# 6WP.net
KiCad netlist of a schematic drawn in EAGLE
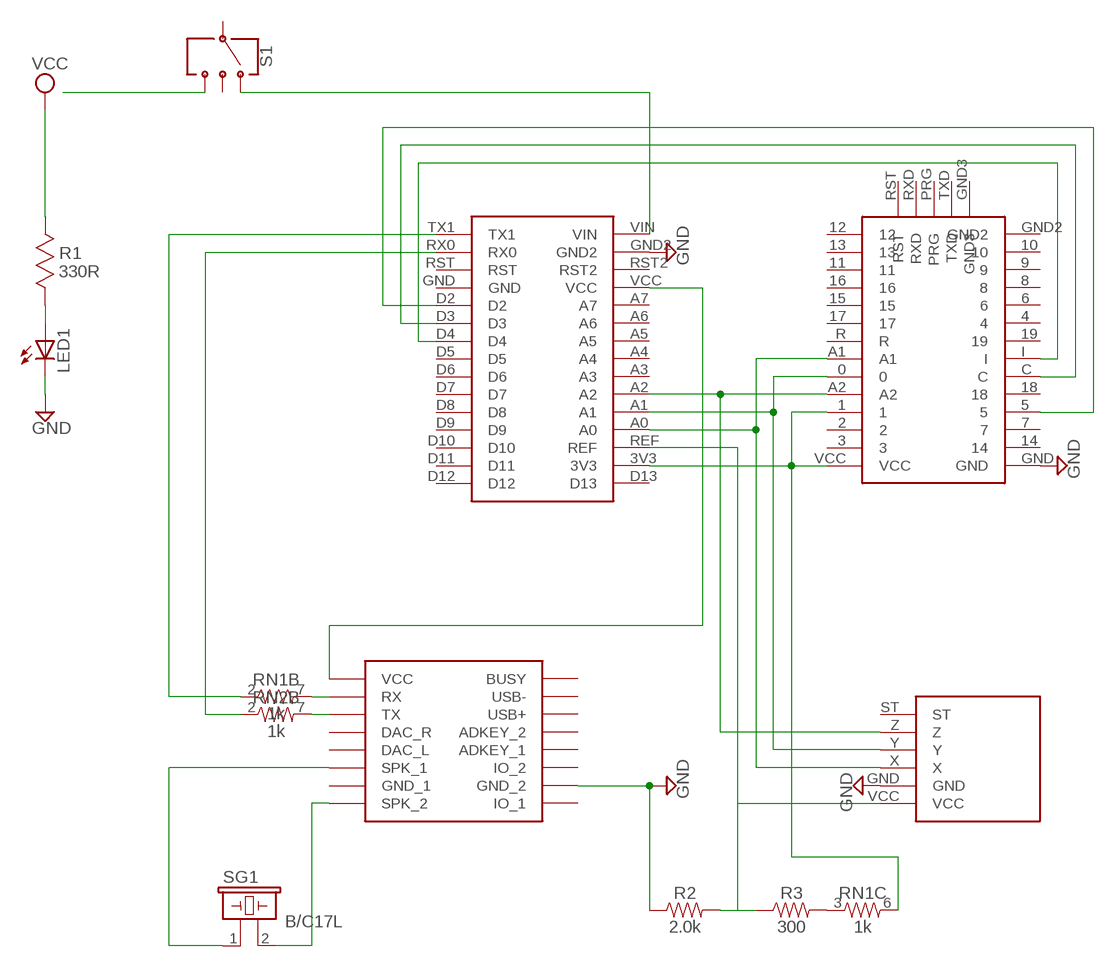
[diagram p0: schematic, sheet 1]
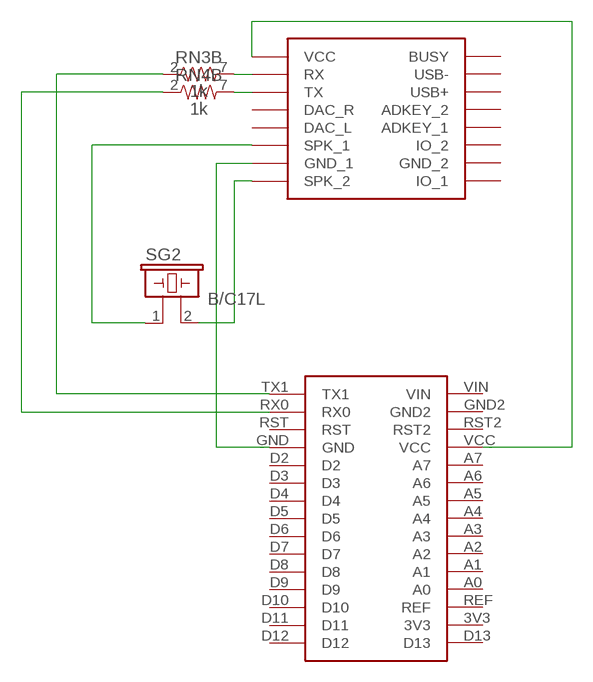
[diagram p1: schematic, sheet 2]

(export (version "E")
  (design (tool "Eeschema 10.0.6"))
  (components
    (comp (ref "A3")
      (value "ARDUINONANO")
      (footprint "eagle-import:ARDUINONANO")
      (libsource (lib "eagle-import") (part "ARDUINONANO"))
    )
    (comp (ref "RN3")
      (value "1k")
      (footprint "eagle-import:0805-ARV")
      (libsource (lib "eagle-import") (part "1KOHM-ARRAY(4)-0805_ARV-1/10W-5%"))
    )
    (comp (ref "RN4")
      (value "1k")
      (footprint "eagle-import:0805-ARV")
      (libsource (lib "eagle-import") (part "1KOHM-ARRAY(4)-0805_ARV-1/10W-5%"))
    )
    (comp (ref "SG2")
      (value "B/C17L")
      (footprint "eagle-import:B_C17L")
      (libsource (lib "eagle-import") (part "B/C17L"))
    )
    (comp (ref "U$1")
      (value "DFPLAYER")
      (footprint "eagle-import:DFPLAYER")
      (libsource (lib "eagle-import") (part "DFPLAYER"))
    )
    (comp (ref "A1")
      (value "ARDUINONANO")
      (footprint "eagle-import:ARDUINONANO")
      (libsource (lib "eagle-import") (part "ARDUINONANO"))
    )
    (comp (ref "A2")
      (value "ADXL335")
      (footprint "eagle-import:ADXL335")
      (libsource (lib "eagle-import") (part "ADXL335"))
    )
    (comp (ref "A4")
      (value "TWELITEDIP")
      (footprint "eagle-import:TWELITEDIP")
      (libsource (lib "eagle-import") (part "TWELITEDIP"))
    )
    (comp (ref "LED1")
      (value "LEDCHIP-LED0603")
      (footprint "eagle-import:CHIP-LED0603")
      (libsource (lib "eagle-import") (part "LEDCHIP-LED0603"))
    )
    (comp (ref "R1")
      (value "330R")
      (footprint "eagle-import:RESC1608X60N")
      (fields (field (name "MPN") "MC0.063W06031%330R") (field (name "TOLERANCE") "±1%"))
      (libsource (lib "eagle-import") (part "MC0.063W06031%330R"))
    )
    (comp (ref "R2")
      (value "2.0k")
      (footprint "eagle-import:0603")
      (libsource (lib "eagle-import") (part "2.0KOHM-0603-1/10W-5%"))
    )
    (comp (ref "R3")
      (value "300")
      (footprint "eagle-import:0603")
      (libsource (lib "eagle-import") (part "300OHM-0603-1/10W-1%"))
    )
    (comp (ref "RN1")
      (value "1k")
      (footprint "eagle-import:0805-ARV")
      (libsource (lib "eagle-import") (part "1KOHM-ARRAY(4)-0805_ARV-1/10W-5%"))
    )
    (comp (ref "RN2")
      (value "1k")
      (footprint "eagle-import:0805-ARV")
      (libsource (lib "eagle-import") (part "1KOHM-ARRAY(4)-0805_ARV-1/10W-5%"))
    )
    (comp (ref "S1")
      (value "SWITCH-SP3T-SMD")
      (footprint "eagle-import:SWITCH_SP3T_SMD")
      (libsource (lib "eagle-import") (part "SWITCH-SP3T-SMD"))
    )
    (comp (ref "SG1")
      (value "B/C17L")
      (footprint "eagle-import:B_C17L")
      (libsource (lib "eagle-import") (part "B/C17L"))
    )
    (comp (ref "U$2")
      (value "DFPLAYER")
      (footprint "eagle-import:DFPLAYER")
      (libsource (lib "eagle-import") (part "DFPLAYER"))
    )
  )
  (nets
    (net (code "1") (name "GND") (class "Default")
      (node (ref "A1") (pin "GND2") (pinfunction "GND2_GND2") (pintype "bidirectional"))
      (node (ref "A2") (pin "GND") (pinfunction "GND_GND") (pintype "bidirectional"))
      (node (ref "A4") (pin "GND") (pinfunction "GND_GND") (pintype "bidirectional"))
      (node (ref "LED1") (pin "C") (pinfunction "C_C") (pintype "passive"))
      (node (ref "R2") (pin "1") (pinfunction "1_1") (pintype "passive"))
      (node (ref "U$2") (pin "GND_2") (pinfunction "GND_2_GND_2") (pintype "bidirectional"))
    )
    (net (code "2") (name "Net-(A1-PadA0)") (class "Default")
      (node (ref "A1") (pin "A0") (pinfunction "A0_A0") (pintype "bidirectional"))
      (node (ref "A2") (pin "X") (pinfunction "X_X") (pintype "bidirectional"))
      (node (ref "A4") (pin "A1") (pinfunction "A1_A1") (pintype "bidirectional"))
    )
    (net (code "3") (name "Net-(A1-PadA1)") (class "Default")
      (node (ref "A1") (pin "A1") (pinfunction "A1_A1") (pintype "bidirectional"))
      (node (ref "A2") (pin "Y") (pinfunction "Y_Y") (pintype "bidirectional"))
      (node (ref "A4") (pin "0") (pinfunction "0_0") (pintype "bidirectional"))
    )
    (net (code "4") (name "Net-(A1-PadA2)") (class "Default")
      (node (ref "A1") (pin "A2") (pinfunction "A2_A2") (pintype "bidirectional"))
      (node (ref "A2") (pin "Z") (pinfunction "Z_Z") (pintype "bidirectional"))
      (node (ref "A4") (pin "A2") (pinfunction "A2_A2") (pintype "bidirectional"))
    )
    (net (code "5") (name "Net-(A1-PadD2)") (class "Default")
      (node (ref "A1") (pin "D2") (pinfunction "D2_D2") (pintype "bidirectional"))
      (node (ref "A4") (pin "5") (pinfunction "5_5") (pintype "bidirectional"))
    )
    (net (code "6") (name "Net-(A1-PadD3)") (class "Default")
      (node (ref "A1") (pin "D3") (pinfunction "D3_D3") (pintype "bidirectional"))
      (node (ref "A4") (pin "C") (pinfunction "C_C") (pintype "bidirectional"))
    )
    (net (code "7") (name "Net-(A1-PadD4)") (class "Default")
      (node (ref "A1") (pin "D4") (pinfunction "D4_D4") (pintype "bidirectional"))
      (node (ref "A4") (pin "I") (pinfunction "I_I") (pintype "bidirectional"))
    )
    (net (code "8") (name "Net-(A1-PadREF)") (class "Default")
      (node (ref "A1") (pin "REF") (pinfunction "REF_REF") (pintype "bidirectional"))
      (node (ref "A2") (pin "VCC") (pinfunction "VCC_VCC") (pintype "bidirectional"))
      (node (ref "R2") (pin "2") (pinfunction "2_2") (pintype "passive"))
      (node (ref "R3") (pin "1") (pinfunction "1_1") (pintype "passive"))
    )
    (net (code "9") (name "Net-(A1-PadVCC)") (class "Default")
      (node (ref "A1") (pin "VCC") (pinfunction "VCC_VCC") (pintype "bidirectional"))
      (node (ref "U$2") (pin "VCC") (pinfunction "VCC_VCC") (pintype "bidirectional"))
    )
    (net (code "10") (name "Net-(A1-PadVIN)") (class "Default")
      (node (ref "A1") (pin "VIN") (pinfunction "VIN_VIN") (pintype "bidirectional"))
      (node (ref "S1") (pin "1") (pinfunction "1_1") (pintype "bidirectional"))
    )
    (net (code "11") (name "Net-(A3-PadGND)") (class "Default")
      (node (ref "A3") (pin "GND") (pinfunction "GND_GND") (pintype "bidirectional"))
      (node (ref "U$1") (pin "GND_1") (pinfunction "GND_1_GND_1") (pintype "bidirectional"))
    )
    (net (code "12") (name "Net-(A3-PadVCC)") (class "Default")
      (node (ref "A3") (pin "VCC") (pinfunction "VCC_VCC") (pintype "bidirectional"))
      (node (ref "U$1") (pin "VCC") (pinfunction "VCC_VCC") (pintype "bidirectional"))
    )
    (net (code "13") (name "Net-(R1-R2)") (class "Default")
      (node (ref "LED1") (pin "A") (pinfunction "A_A") (pintype "passive"))
      (node (ref "R1") (pin "2") (pinfunction "R2_2") (pintype "passive"))
    )
    (net (code "14") (name "Net-(RN1B-1)") (class "Default")
      (node (ref "A1") (pin "TX1") (pinfunction "TX1_TX1") (pintype "bidirectional"))
      (node (ref "RN1") (pin "2") (pinfunction "1_2") (pintype "passive"))
    )
    (net (code "15") (name "Net-(RN1B-2)") (class "Default")
      (node (ref "RN1") (pin "7") (pinfunction "2_7") (pintype "passive"))
      (node (ref "U$2") (pin "RX") (pinfunction "RX_RX") (pintype "bidirectional"))
    )
    (net (code "16") (name "Net-(RN1C-1)") (class "Default")
      (node (ref "R3") (pin "2") (pinfunction "2_2") (pintype "passive"))
      (node (ref "RN1") (pin "3") (pinfunction "1_3") (pintype "passive"))
    )
    (net (code "17") (name "Net-(RN1C-2)") (class "Default")
      (node (ref "A1") (pin "3V3") (pinfunction "3V3_3V3") (pintype "bidirectional"))
      (node (ref "A4") (pin "1") (pinfunction "1_1") (pintype "bidirectional"))
      (node (ref "A4") (pin "VCC") (pinfunction "VCC_VCC") (pintype "bidirectional"))
      (node (ref "RN1") (pin "6") (pinfunction "2_6") (pintype "passive"))
    )
    (net (code "18") (name "Net-(RN2B-1)") (class "Default")
      (node (ref "A1") (pin "RX0") (pinfunction "RX0_RX0") (pintype "bidirectional"))
      (node (ref "RN2") (pin "2") (pinfunction "1_2") (pintype "passive"))
    )
    (net (code "19") (name "Net-(RN2B-2)") (class "Default")
      (node (ref "RN2") (pin "7") (pinfunction "2_7") (pintype "passive"))
      (node (ref "U$2") (pin "TX") (pinfunction "TX_TX") (pintype "bidirectional"))
    )
    (net (code "20") (name "Net-(RN3B-1)") (class "Default")
      (node (ref "A3") (pin "TX1") (pinfunction "TX1_TX1") (pintype "bidirectional"))
      (node (ref "RN3") (pin "2") (pinfunction "1_2") (pintype "passive"))
    )
    (net (code "21") (name "Net-(RN3B-2)") (class "Default")
      (node (ref "RN3") (pin "7") (pinfunction "2_7") (pintype "passive"))
      (node (ref "U$1") (pin "RX") (pinfunction "RX_RX") (pintype "bidirectional"))
    )
    (net (code "22") (name "Net-(RN4B-1)") (class "Default")
      (node (ref "A3") (pin "RX0") (pinfunction "RX0_RX0") (pintype "bidirectional"))
      (node (ref "RN4") (pin "2") (pinfunction "1_2") (pintype "passive"))
    )
    (net (code "23") (name "Net-(RN4B-2)") (class "Default")
      (node (ref "RN4") (pin "7") (pinfunction "2_7") (pintype "passive"))
      (node (ref "U$1") (pin "TX") (pinfunction "TX_TX") (pintype "bidirectional"))
    )
    (net (code "24") (name "Net-(U$1-SPK_1)") (class "Default")
      (node (ref "SG2") (pin "1") (pinfunction "1_1") (pintype "passive"))
      (node (ref "U$1") (pin "SPK1") (pinfunction "SPK_1_SPK1") (pintype "bidirectional"))
    )
    (net (code "25") (name "Net-(U$1-SPK_2)") (class "Default")
      (node (ref "SG2") (pin "2") (pinfunction "2_2") (pintype "passive"))
      (node (ref "U$1") (pin "SPK2") (pinfunction "SPK_2_SPK2") (pintype "bidirectional"))
    )
    (net (code "26") (name "Net-(U$2-SPK_1)") (class "Default")
      (node (ref "SG1") (pin "1") (pinfunction "1_1") (pintype "passive"))
      (node (ref "U$2") (pin "SPK1") (pinfunction "SPK_1_SPK1") (pintype "bidirectional"))
    )
    (net (code "27") (name "Net-(U$2-SPK_2)") (class "Default")
      (node (ref "SG1") (pin "2") (pinfunction "2_2") (pintype "passive"))
      (node (ref "U$2") (pin "SPK2") (pinfunction "SPK_2_SPK2") (pintype "bidirectional"))
    )
    (net (code "28") (name "VCC") (class "Default")
      (node (ref "R1") (pin "1") (pinfunction "R1_1") (pintype "passive"))
    )
    (net (code "29") (name "unconnected-(A1-PadA3)") (class "Default")
      (node (ref "A1") (pin "A3") (pinfunction "A3_A3") (pintype "bidirectional"))
    )
    (net (code "30") (name "unconnected-(A1-PadA4)") (class "Default")
      (node (ref "A1") (pin "A4") (pinfunction "A4_A4") (pintype "bidirectional"))
    )
    (net (code "31") (name "unconnected-(A1-PadA5)") (class "Default")
      (node (ref "A1") (pin "A5") (pinfunction "A5_A5") (pintype "bidirectional"))
    )
    (net (code "32") (name "unconnected-(A1-PadA6)") (class "Default")
      (node (ref "A1") (pin "A6") (pinfunction "A6_A6") (pintype "bidirectional"))
    )
    (net (code "33") (name "unconnected-(A1-PadA7)") (class "Default")
      (node (ref "A1") (pin "A7") (pinfunction "A7_A7") (pintype "bidirectional"))
    )
    (net (code "34") (name "unconnected-(A1-PadD5)") (class "Default")
      (node (ref "A1") (pin "D5") (pinfunction "D5_D5") (pintype "bidirectional"))
    )
    (net (code "35") (name "unconnected-(A1-PadD6)") (class "Default")
      (node (ref "A1") (pin "D6") (pinfunction "D6_D6") (pintype "bidirectional"))
    )
    (net (code "36") (name "unconnected-(A1-PadD7)") (class "Default")
      (node (ref "A1") (pin "D7") (pinfunction "D7_D7") (pintype "bidirectional"))
    )
    (net (code "37") (name "unconnected-(A1-PadD8)") (class "Default")
      (node (ref "A1") (pin "D8") (pinfunction "D8_D8") (pintype "bidirectional"))
    )
    (net (code "38") (name "unconnected-(A1-PadD9)") (class "Default")
      (node (ref "A1") (pin "D9") (pinfunction "D9_D9") (pintype "bidirectional"))
    )
    (net (code "39") (name "unconnected-(A1-PadD10)") (class "Default")
      (node (ref "A1") (pin "D10") (pinfunction "D10_D10") (pintype "bidirectional"))
    )
    (net (code "40") (name "unconnected-(A1-PadD11)") (class "Default")
      (node (ref "A1") (pin "D11") (pinfunction "D11_D11") (pintype "bidirectional"))
    )
    (net (code "41") (name "unconnected-(A1-PadD12)") (class "Default")
      (node (ref "A1") (pin "D12") (pinfunction "D12_D12") (pintype "bidirectional"))
    )
    (net (code "42") (name "unconnected-(A1-PadD13)") (class "Default")
      (node (ref "A1") (pin "D13") (pinfunction "D13_D13") (pintype "bidirectional"))
    )
    (net (code "43") (name "unconnected-(A1-PadGND)") (class "Default")
      (node (ref "A1") (pin "GND") (pinfunction "GND_GND") (pintype "bidirectional"))
    )
    (net (code "44") (name "unconnected-(A1-PadRST)") (class "Default")
      (node (ref "A1") (pin "RST") (pinfunction "RST_RST") (pintype "bidirectional"))
    )
    (net (code "45") (name "unconnected-(A1-PadRST2)") (class "Default")
      (node (ref "A1") (pin "RST2") (pinfunction "RST2_RST2") (pintype "bidirectional"))
    )
    (net (code "46") (name "unconnected-(A2-PadST)") (class "Default")
      (node (ref "A2") (pin "ST") (pinfunction "ST_ST") (pintype "bidirectional"))
    )
    (net (code "47") (name "unconnected-(A3-Pad3V3)") (class "Default")
      (node (ref "A3") (pin "3V3") (pinfunction "3V3_3V3") (pintype "bidirectional"))
    )
    (net (code "48") (name "unconnected-(A3-PadA0)") (class "Default")
      (node (ref "A3") (pin "A0") (pinfunction "A0_A0") (pintype "bidirectional"))
    )
    (net (code "49") (name "unconnected-(A3-PadA1)") (class "Default")
      (node (ref "A3") (pin "A1") (pinfunction "A1_A1") (pintype "bidirectional"))
    )
    (net (code "50") (name "unconnected-(A3-PadA2)") (class "Default")
      (node (ref "A3") (pin "A2") (pinfunction "A2_A2") (pintype "bidirectional"))
    )
    (net (code "51") (name "unconnected-(A3-PadA3)") (class "Default")
      (node (ref "A3") (pin "A3") (pinfunction "A3_A3") (pintype "bidirectional"))
    )
    (net (code "52") (name "unconnected-(A3-PadA4)") (class "Default")
      (node (ref "A3") (pin "A4") (pinfunction "A4_A4") (pintype "bidirectional"))
    )
    (net (code "53") (name "unconnected-(A3-PadA5)") (class "Default")
      (node (ref "A3") (pin "A5") (pinfunction "A5_A5") (pintype "bidirectional"))
    )
    (net (code "54") (name "unconnected-(A3-PadA6)") (class "Default")
      (node (ref "A3") (pin "A6") (pinfunction "A6_A6") (pintype "bidirectional"))
    )
    (net (code "55") (name "unconnected-(A3-PadA7)") (class "Default")
      (node (ref "A3") (pin "A7") (pinfunction "A7_A7") (pintype "bidirectional"))
    )
    (net (code "56") (name "unconnected-(A3-PadD2)") (class "Default")
      (node (ref "A3") (pin "D2") (pinfunction "D2_D2") (pintype "bidirectional"))
    )
    (net (code "57") (name "unconnected-(A3-PadD3)") (class "Default")
      (node (ref "A3") (pin "D3") (pinfunction "D3_D3") (pintype "bidirectional"))
    )
    (net (code "58") (name "unconnected-(A3-PadD4)") (class "Default")
      (node (ref "A3") (pin "D4") (pinfunction "D4_D4") (pintype "bidirectional"))
    )
    (net (code "59") (name "unconnected-(A3-PadD5)") (class "Default")
      (node (ref "A3") (pin "D5") (pinfunction "D5_D5") (pintype "bidirectional"))
    )
    (net (code "60") (name "unconnected-(A3-PadD6)") (class "Default")
      (node (ref "A3") (pin "D6") (pinfunction "D6_D6") (pintype "bidirectional"))
    )
    (net (code "61") (name "unconnected-(A3-PadD7)") (class "Default")
      (node (ref "A3") (pin "D7") (pinfunction "D7_D7") (pintype "bidirectional"))
    )
    (net (code "62") (name "unconnected-(A3-PadD8)") (class "Default")
      (node (ref "A3") (pin "D8") (pinfunction "D8_D8") (pintype "bidirectional"))
    )
    (net (code "63") (name "unconnected-(A3-PadD9)") (class "Default")
      (node (ref "A3") (pin "D9") (pinfunction "D9_D9") (pintype "bidirectional"))
    )
    (net (code "64") (name "unconnected-(A3-PadD10)") (class "Default")
      (node (ref "A3") (pin "D10") (pinfunction "D10_D10") (pintype "bidirectional"))
    )
    (net (code "65") (name "unconnected-(A3-PadD11)") (class "Default")
      (node (ref "A3") (pin "D11") (pinfunction "D11_D11") (pintype "bidirectional"))
    )
    (net (code "66") (name "unconnected-(A3-PadD12)") (class "Default")
      (node (ref "A3") (pin "D12") (pinfunction "D12_D12") (pintype "bidirectional"))
    )
    (net (code "67") (name "unconnected-(A3-PadD13)") (class "Default")
      (node (ref "A3") (pin "D13") (pinfunction "D13_D13") (pintype "bidirectional"))
    )
    (net (code "68") (name "unconnected-(A3-PadGND2)") (class "Default")
      (node (ref "A3") (pin "GND2") (pinfunction "GND2_GND2") (pintype "bidirectional"))
    )
    (net (code "69") (name "unconnected-(A3-PadREF)") (class "Default")
      (node (ref "A3") (pin "REF") (pinfunction "REF_REF") (pintype "bidirectional"))
    )
    (net (code "70") (name "unconnected-(A3-PadRST)") (class "Default")
      (node (ref "A3") (pin "RST") (pinfunction "RST_RST") (pintype "bidirectional"))
    )
    (net (code "71") (name "unconnected-(A3-PadRST2)") (class "Default")
      (node (ref "A3") (pin "RST2") (pinfunction "RST2_RST2") (pintype "bidirectional"))
    )
    (net (code "72") (name "unconnected-(A3-PadVIN)") (class "Default")
      (node (ref "A3") (pin "VIN") (pinfunction "VIN_VIN") (pintype "bidirectional"))
    )
    (net (code "73") (name "unconnected-(A4-Pad2)") (class "Default")
      (node (ref "A4") (pin "2") (pinfunction "2_2") (pintype "bidirectional"))
    )
    (net (code "74") (name "unconnected-(A4-Pad3)") (class "Default")
      (node (ref "A4") (pin "3") (pinfunction "3_3") (pintype "bidirectional"))
    )
    (net (code "75") (name "unconnected-(A4-Pad4)") (class "Default")
      (node (ref "A4") (pin "4") (pinfunction "4_4") (pintype "bidirectional"))
    )
    (net (code "76") (name "unconnected-(A4-Pad6)") (class "Default")
      (node (ref "A4") (pin "6") (pinfunction "6_6") (pintype "bidirectional"))
    )
    (net (code "77") (name "unconnected-(A4-Pad7)") (class "Default")
      (node (ref "A4") (pin "7") (pinfunction "7_7") (pintype "bidirectional"))
    )
    (net (code "78") (name "unconnected-(A4-Pad8)") (class "Default")
      (node (ref "A4") (pin "8") (pinfunction "8_8") (pintype "bidirectional"))
    )
    (net (code "79") (name "unconnected-(A4-Pad9)") (class "Default")
      (node (ref "A4") (pin "9") (pinfunction "9_9") (pintype "bidirectional"))
    )
    (net (code "80") (name "unconnected-(A4-Pad10)") (class "Default")
      (node (ref "A4") (pin "10") (pinfunction "10_10") (pintype "bidirectional"))
    )
    (net (code "81") (name "unconnected-(A4-Pad11)") (class "Default")
      (node (ref "A4") (pin "11") (pinfunction "11_11") (pintype "bidirectional"))
    )
    (net (code "82") (name "unconnected-(A4-Pad12)") (class "Default")
      (node (ref "A4") (pin "12") (pinfunction "12_12") (pintype "bidirectional"))
    )
    (net (code "83") (name "unconnected-(A4-Pad13)") (class "Default")
      (node (ref "A4") (pin "13") (pinfunction "13_13") (pintype "bidirectional"))
    )
    (net (code "84") (name "unconnected-(A4-Pad14)") (class "Default")
      (node (ref "A4") (pin "14") (pinfunction "14_14") (pintype "bidirectional"))
    )
    (net (code "85") (name "unconnected-(A4-Pad15)") (class "Default")
      (node (ref "A4") (pin "15") (pinfunction "15_15") (pintype "bidirectional"))
    )
    (net (code "86") (name "unconnected-(A4-Pad16)") (class "Default")
      (node (ref "A4") (pin "16") (pinfunction "16_16") (pintype "bidirectional"))
    )
    (net (code "87") (name "unconnected-(A4-Pad17)") (class "Default")
      (node (ref "A4") (pin "17") (pinfunction "17_17") (pintype "bidirectional"))
    )
    (net (code "88") (name "unconnected-(A4-Pad18)") (class "Default")
      (node (ref "A4") (pin "18") (pinfunction "18_18") (pintype "bidirectional"))
    )
    (net (code "89") (name "unconnected-(A4-Pad19)") (class "Default")
      (node (ref "A4") (pin "19") (pinfunction "19_19") (pintype "bidirectional"))
    )
    (net (code "90") (name "unconnected-(A4-PadGND2)") (class "Default")
      (node (ref "A4") (pin "GND2") (pinfunction "GND2_GND2") (pintype "bidirectional"))
    )
    (net (code "91") (name "unconnected-(A4-PadGND3)") (class "Default")
      (node (ref "A4") (pin "GND3") (pinfunction "GND3_GND3") (pintype "bidirectional"))
    )
    (net (code "92") (name "unconnected-(A4-PadPRG)") (class "Default")
      (node (ref "A4") (pin "PRG") (pinfunction "PRG_PRG") (pintype "bidirectional"))
    )
    (net (code "93") (name "unconnected-(A4-PadR)") (class "Default")
      (node (ref "A4") (pin "R") (pinfunction "R_R") (pintype "bidirectional"))
    )
    (net (code "94") (name "unconnected-(A4-PadRST)") (class "Default")
      (node (ref "A4") (pin "RST") (pinfunction "RST_RST") (pintype "bidirectional"))
    )
    (net (code "95") (name "unconnected-(A4-PadRXD)") (class "Default")
      (node (ref "A4") (pin "RXD") (pinfunction "RXD_RXD") (pintype "bidirectional"))
    )
    (net (code "96") (name "unconnected-(A4-PadTXD)") (class "Default")
      (node (ref "A4") (pin "TXD") (pinfunction "TXD_TXD") (pintype "bidirectional"))
    )
    (net (code "97") (name "unconnected-(S1-Pad2)") (class "Default")
      (node (ref "S1") (pin "2") (pinfunction "2_2") (pintype "bidirectional"))
    )
    (net (code "98") (name "unconnected-(S1-Pad3)") (class "Default")
      (node (ref "S1") (pin "3") (pinfunction "3_3") (pintype "bidirectional"))
    )
    (net (code "99") (name "unconnected-(S1-Pad4)") (class "Default")
      (node (ref "S1") (pin "4") (pinfunction "4_4") (pintype "bidirectional"))
    )
    (net (code "100") (name "unconnected-(U$1-ADKEY_1-PadADKEY1)") (class "Default")
      (node (ref "U$1") (pin "ADKEY1") (pinfunction "ADKEY_1_ADKEY1") (pintype "bidirectional"))
    )
    (net (code "101") (name "unconnected-(U$1-ADKEY_2-PadADKEY2)") (class "Default")
      (node (ref "U$1") (pin "ADKEY2") (pinfunction "ADKEY_2_ADKEY2") (pintype "bidirectional"))
    )
    (net (code "102") (name "unconnected-(U$1-IO_1-PadIO1)") (class "Default")
      (node (ref "U$1") (pin "IO1") (pinfunction "IO_1_IO1") (pintype "bidirectional"))
    )
    (net (code "103") (name "unconnected-(U$1-IO_2-PadIO2)") (class "Default")
      (node (ref "U$1") (pin "IO2") (pinfunction "IO_2_IO2") (pintype "bidirectional"))
    )
    (net (code "104") (name "unconnected-(U$1-PadBUSY)") (class "Default")
      (node (ref "U$1") (pin "BUSY") (pinfunction "BUSY_BUSY") (pintype "bidirectional"))
    )
    (net (code "105") (name "unconnected-(U$1-PadDAC_L)") (class "Default")
      (node (ref "U$1") (pin "DAC_L") (pinfunction "DAC_L_DAC_L") (pintype "bidirectional"))
    )
    (net (code "106") (name "unconnected-(U$1-PadDAC_R)") (class "Default")
      (node (ref "U$1") (pin "DAC_R") (pinfunction "DAC_R_DAC_R") (pintype "bidirectional"))
    )
    (net (code "107") (name "unconnected-(U$1-PadGND_2)") (class "Default")
      (node (ref "U$1") (pin "GND_2") (pinfunction "GND_2_GND_2") (pintype "bidirectional"))
    )
    (net (code "108") (name "unconnected-(U$1-PadUSB+)") (class "Default")
      (node (ref "U$1") (pin "USB+") (pinfunction "USB+_USB+") (pintype "bidirectional"))
    )
    (net (code "109") (name "unconnected-(U$1-PadUSB-)") (class "Default")
      (node (ref "U$1") (pin "USB-") (pinfunction "USB-_USB-") (pintype "bidirectional"))
    )
    (net (code "110") (name "unconnected-(U$2-ADKEY_1-PadADKEY1)") (class "Default")
      (node (ref "U$2") (pin "ADKEY1") (pinfunction "ADKEY_1_ADKEY1") (pintype "bidirectional"))
    )
    (net (code "111") (name "unconnected-(U$2-ADKEY_2-PadADKEY2)") (class "Default")
      (node (ref "U$2") (pin "ADKEY2") (pinfunction "ADKEY_2_ADKEY2") (pintype "bidirectional"))
    )
    (net (code "112") (name "unconnected-(U$2-IO_1-PadIO1)") (class "Default")
      (node (ref "U$2") (pin "IO1") (pinfunction "IO_1_IO1") (pintype "bidirectional"))
    )
    (net (code "113") (name "unconnected-(U$2-IO_2-PadIO2)") (class "Default")
      (node (ref "U$2") (pin "IO2") (pinfunction "IO_2_IO2") (pintype "bidirectional"))
    )
    (net (code "114") (name "unconnected-(U$2-PadBUSY)") (class "Default")
      (node (ref "U$2") (pin "BUSY") (pinfunction "BUSY_BUSY") (pintype "bidirectional"))
    )
    (net (code "115") (name "unconnected-(U$2-PadDAC_L)") (class "Default")
      (node (ref "U$2") (pin "DAC_L") (pinfunction "DAC_L_DAC_L") (pintype "bidirectional"))
    )
    (net (code "116") (name "unconnected-(U$2-PadDAC_R)") (class "Default")
      (node (ref "U$2") (pin "DAC_R") (pinfunction "DAC_R_DAC_R") (pintype "bidirectional"))
    )
    (net (code "117") (name "unconnected-(U$2-PadGND_1)") (class "Default")
      (node (ref "U$2") (pin "GND_1") (pinfunction "GND_1_GND_1") (pintype "bidirectional"))
    )
    (net (code "118") (name "unconnected-(U$2-PadUSB+)") (class "Default")
      (node (ref "U$2") (pin "USB+") (pinfunction "USB+_USB+") (pintype "bidirectional"))
    )
    (net (code "119") (name "unconnected-(U$2-PadUSB-)") (class "Default")
      (node (ref "U$2") (pin "USB-") (pinfunction "USB-_USB-") (pintype "bidirectional"))
    )
  )
)
